# fire-fly.net
KiCad netlist of a schematic drawn in EAGLE
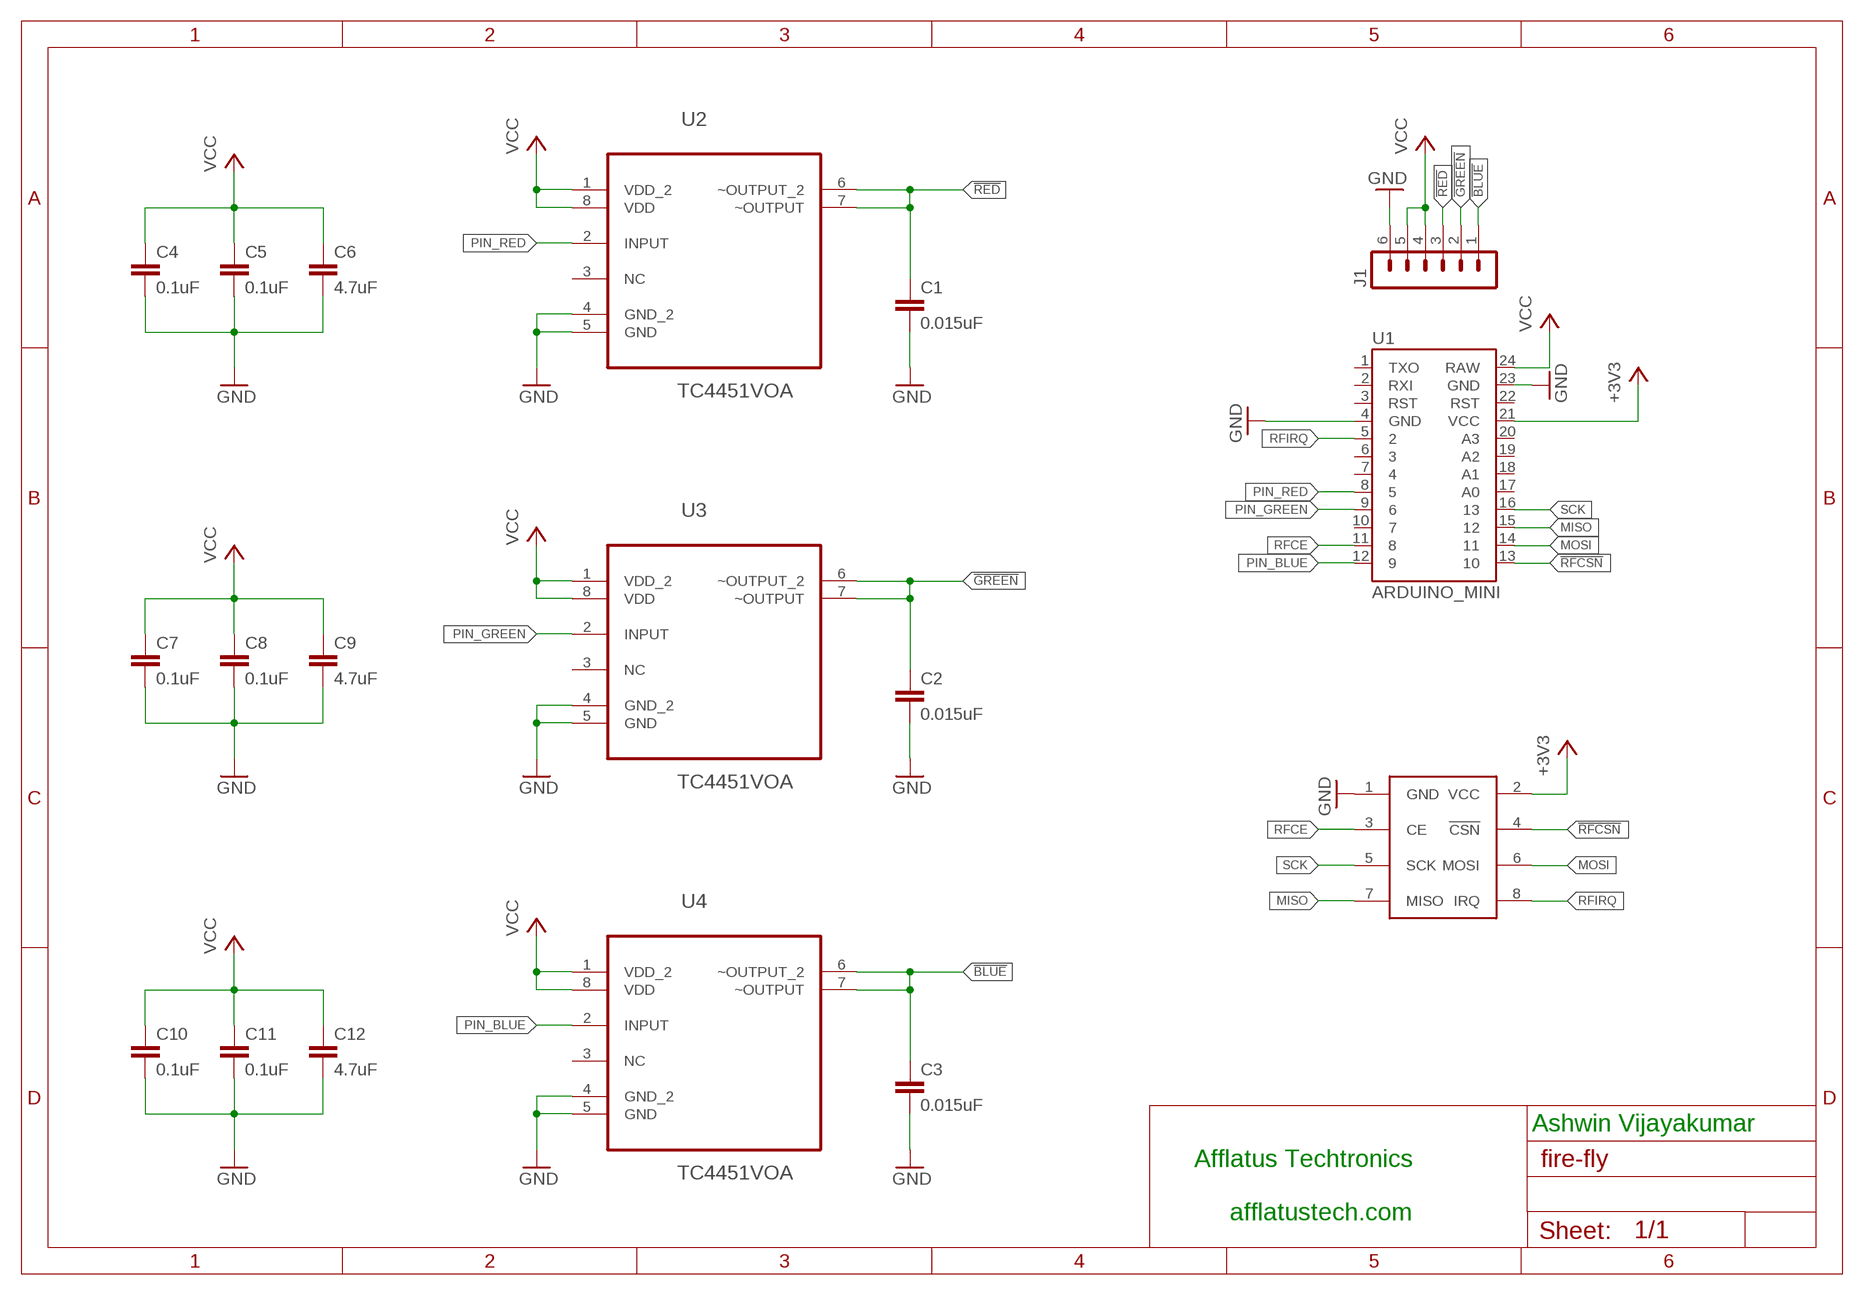
[diagram p0: schematic, sheet 1]

(export (version "E")
  (design (tool "Eeschema 10.0.6"))
  (components
    (comp (ref "C1")
      (value "0.015uF")
      (footprint "eagle-import:C1206")
      (libsource (lib "eagle-import") (part "C-EUC1206"))
    )
    (comp (ref "C2")
      (value "0.015uF")
      (footprint "eagle-import:C1206")
      (libsource (lib "eagle-import") (part "C-EUC1206"))
    )
    (comp (ref "C3")
      (value "0.015uF")
      (footprint "eagle-import:C1206")
      (libsource (lib "eagle-import") (part "C-EUC1206"))
    )
    (comp (ref "C4")
      (value "0.1uF")
      (footprint "eagle-import:C1206")
      (libsource (lib "eagle-import") (part "C-EUC1206"))
    )
    (comp (ref "C5")
      (value "0.1uF")
      (footprint "eagle-import:C1206")
      (libsource (lib "eagle-import") (part "C-EUC1206"))
    )
    (comp (ref "C6")
      (value "4.7uF")
      (footprint "eagle-import:C1206")
      (libsource (lib "eagle-import") (part "C-EUC1206"))
    )
    (comp (ref "C7")
      (value "0.1uF")
      (footprint "eagle-import:C1206")
      (libsource (lib "eagle-import") (part "C-EUC1206"))
    )
    (comp (ref "C8")
      (value "0.1uF")
      (footprint "eagle-import:C1206")
      (libsource (lib "eagle-import") (part "C-EUC1206"))
    )
    (comp (ref "C9")
      (value "4.7uF")
      (footprint "eagle-import:C1206")
      (libsource (lib "eagle-import") (part "C-EUC1206"))
    )
    (comp (ref "C10")
      (value "0.1uF")
      (footprint "eagle-import:C1206")
      (libsource (lib "eagle-import") (part "C-EUC1206"))
    )
    (comp (ref "C11")
      (value "0.1uF")
      (footprint "eagle-import:C1206")
      (libsource (lib "eagle-import") (part "C-EUC1206"))
    )
    (comp (ref "C12")
      (value "4.7uF")
      (footprint "eagle-import:C1206")
      (libsource (lib "eagle-import") (part "C-EUC1206"))
    )
    (comp (ref "J1")
      (value "MA06-1")
      (footprint "eagle-import:MA06-1")
      (libsource (lib "eagle-import") (part "MA06-1"))
    )
    (comp (ref "U$1")
      (value "NRF24L01_MODULE")
      (footprint "eagle-import:NRF24L01_MODULE")
      (libsource (lib "eagle-import") (part "NRF24L01_MODULE"))
    )
    (comp (ref "U1")
      (value "ARDUINO_MINI")
      (footprint "eagle-import:ARDUINO_MINI")
      (libsource (lib "eagle-import") (part "ARDUINO_MINI"))
    )
    (comp (ref "U2")
      (value "TC4451VOA")
      (footprint "eagle-import:SOIC127P600X175-8N")
      (libsource (lib "eagle-import") (part "TC4451VOA"))
    )
    (comp (ref "U3")
      (value "TC4451VOA")
      (footprint "eagle-import:SOIC127P600X175-8N")
      (libsource (lib "eagle-import") (part "TC4451VOA"))
    )
    (comp (ref "U4")
      (value "TC4451VOA")
      (footprint "eagle-import:SOIC127P600X175-8N")
      (libsource (lib "eagle-import") (part "TC4451VOA"))
    )
  )
  (nets
    (net (code "1") (name "+3V3") (class "Default")
      (node (ref "U$1") (pin "2") (pinfunction "VCC_2") (pintype "power_in"))
      (node (ref "U1") (pin "21") (pinfunction "VCC_21") (pintype "bidirectional"))
    )
    (net (code "2") (name "/~{BLUE}") (class "Default")
      (node (ref "C3") (pin "1") (pinfunction "1_1") (pintype "passive"))
      (node (ref "J1") (pin "1") (pinfunction "1_1") (pintype "passive"))
      (node (ref "U4") (pin "6") (pinfunction "~{OUTPUT_2}_6") (pintype "output"))
      (node (ref "U4") (pin "7") (pinfunction "~{OUTPUT}_7") (pintype "output"))
    )
    (net (code "3") (name "/~{GREEN}") (class "Default")
      (node (ref "C2") (pin "1") (pinfunction "1_1") (pintype "passive"))
      (node (ref "J1") (pin "2") (pinfunction "2_2") (pintype "passive"))
      (node (ref "U3") (pin "6") (pinfunction "~{OUTPUT_2}_6") (pintype "output"))
      (node (ref "U3") (pin "7") (pinfunction "~{OUTPUT}_7") (pintype "output"))
    )
    (net (code "4") (name "/~{RED}") (class "Default")
      (node (ref "C1") (pin "1") (pinfunction "1_1") (pintype "passive"))
      (node (ref "J1") (pin "3") (pinfunction "3_3") (pintype "passive"))
      (node (ref "U2") (pin "6") (pinfunction "~{OUTPUT_2}_6") (pintype "output"))
      (node (ref "U2") (pin "7") (pinfunction "~{OUTPUT}_7") (pintype "output"))
    )
    (net (code "5") (name "/~{RFCSN}") (class "Default")
      (node (ref "U$1") (pin "4") (pinfunction "~{CSN}_4") (pintype "input"))
      (node (ref "U1") (pin "13") (pinfunction "10_13") (pintype "bidirectional"))
    )
    (net (code "6") (name "GND") (class "Default")
      (node (ref "C1") (pin "2") (pinfunction "2_2") (pintype "passive"))
      (node (ref "C10") (pin "2") (pinfunction "2_2") (pintype "passive"))
      (node (ref "C11") (pin "2") (pinfunction "2_2") (pintype "passive"))
      (node (ref "C12") (pin "2") (pinfunction "2_2") (pintype "passive"))
      (node (ref "C2") (pin "2") (pinfunction "2_2") (pintype "passive"))
      (node (ref "C3") (pin "2") (pinfunction "2_2") (pintype "passive"))
      (node (ref "C4") (pin "2") (pinfunction "2_2") (pintype "passive"))
      (node (ref "C5") (pin "2") (pinfunction "2_2") (pintype "passive"))
      (node (ref "C6") (pin "2") (pinfunction "2_2") (pintype "passive"))
      (node (ref "C7") (pin "2") (pinfunction "2_2") (pintype "passive"))
      (node (ref "C8") (pin "2") (pinfunction "2_2") (pintype "passive"))
      (node (ref "C9") (pin "2") (pinfunction "2_2") (pintype "passive"))
      (node (ref "J1") (pin "6") (pinfunction "6_6") (pintype "passive"))
      (node (ref "U$1") (pin "1") (pinfunction "GND_1") (pintype "power_in"))
      (node (ref "U1") (pin "23") (pinfunction "GND_23") (pintype "bidirectional"))
      (node (ref "U1") (pin "4") (pinfunction "GND_4") (pintype "bidirectional"))
      (node (ref "U2") (pin "4") (pinfunction "GND_2_4") (pintype "passive"))
      (node (ref "U2") (pin "5") (pinfunction "GND_5") (pintype "passive"))
      (node (ref "U3") (pin "4") (pinfunction "GND_2_4") (pintype "passive"))
      (node (ref "U3") (pin "5") (pinfunction "GND_5") (pintype "passive"))
      (node (ref "U4") (pin "4") (pinfunction "GND_2_4") (pintype "passive"))
      (node (ref "U4") (pin "5") (pinfunction "GND_5") (pintype "passive"))
    )
    (net (code "7") (name "MISO") (class "Default")
      (node (ref "U$1") (pin "7") (pinfunction "MISO_7") (pintype "output"))
      (node (ref "U1") (pin "15") (pinfunction "12_15") (pintype "bidirectional"))
    )
    (net (code "8") (name "MOSI") (class "Default")
      (node (ref "U$1") (pin "6") (pinfunction "MOSI_6") (pintype "input"))
      (node (ref "U1") (pin "14") (pinfunction "11_14") (pintype "bidirectional"))
    )
    (net (code "9") (name "PIN_BLUE") (class "Default")
      (node (ref "U1") (pin "12") (pinfunction "9_12") (pintype "bidirectional"))
      (node (ref "U4") (pin "2") (pinfunction "INPUT_2") (pintype "input"))
    )
    (net (code "10") (name "PIN_GREEN") (class "Default")
      (node (ref "U1") (pin "9") (pinfunction "6_9") (pintype "bidirectional"))
      (node (ref "U3") (pin "2") (pinfunction "INPUT_2") (pintype "input"))
    )
    (net (code "11") (name "PIN_RED") (class "Default")
      (node (ref "U1") (pin "8") (pinfunction "5_8") (pintype "bidirectional"))
      (node (ref "U2") (pin "2") (pinfunction "INPUT_2") (pintype "input"))
    )
    (net (code "12") (name "RFCE") (class "Default")
      (node (ref "U$1") (pin "3") (pinfunction "CE_3") (pintype "input"))
      (node (ref "U1") (pin "11") (pinfunction "8_11") (pintype "bidirectional"))
    )
    (net (code "13") (name "RFIRQ") (class "Default")
      (node (ref "U$1") (pin "8") (pinfunction "IRQ_8") (pintype "output"))
      (node (ref "U1") (pin "5") (pinfunction "2_5") (pintype "bidirectional"))
    )
    (net (code "14") (name "SCK") (class "Default")
      (node (ref "U$1") (pin "5") (pinfunction "SCK_5") (pintype "input"))
      (node (ref "U1") (pin "16") (pinfunction "13_16") (pintype "bidirectional"))
    )
    (net (code "15") (name "VCC") (class "Default")
      (node (ref "C10") (pin "1") (pinfunction "1_1") (pintype "passive"))
      (node (ref "C11") (pin "1") (pinfunction "1_1") (pintype "passive"))
      (node (ref "C12") (pin "1") (pinfunction "1_1") (pintype "passive"))
      (node (ref "C4") (pin "1") (pinfunction "1_1") (pintype "passive"))
      (node (ref "C5") (pin "1") (pinfunction "1_1") (pintype "passive"))
      (node (ref "C6") (pin "1") (pinfunction "1_1") (pintype "passive"))
      (node (ref "C7") (pin "1") (pinfunction "1_1") (pintype "passive"))
      (node (ref "C8") (pin "1") (pinfunction "1_1") (pintype "passive"))
      (node (ref "C9") (pin "1") (pinfunction "1_1") (pintype "passive"))
      (node (ref "J1") (pin "4") (pinfunction "4_4") (pintype "passive"))
      (node (ref "J1") (pin "5") (pinfunction "5_5") (pintype "passive"))
      (node (ref "U1") (pin "24") (pinfunction "RAW_24") (pintype "bidirectional"))
      (node (ref "U2") (pin "1") (pinfunction "VDD_2_1") (pintype "power_in"))
      (node (ref "U2") (pin "8") (pinfunction "VDD_8") (pintype "power_in"))
      (node (ref "U3") (pin "1") (pinfunction "VDD_2_1") (pintype "power_in"))
      (node (ref "U3") (pin "8") (pinfunction "VDD_8") (pintype "power_in"))
      (node (ref "U4") (pin "1") (pinfunction "VDD_2_1") (pintype "power_in"))
      (node (ref "U4") (pin "8") (pinfunction "VDD_8") (pintype "power_in"))
    )
    (net (code "16") (name "unconnected-(U1-3-Pad6)") (class "Default")
      (node (ref "U1") (pin "6") (pinfunction "3_6") (pintype "bidirectional"))
    )
    (net (code "17") (name "unconnected-(U1-4-Pad7)") (class "Default")
      (node (ref "U1") (pin "7") (pinfunction "4_7") (pintype "bidirectional"))
    )
    (net (code "18") (name "unconnected-(U1-7-Pad10)") (class "Default")
      (node (ref "U1") (pin "10") (pinfunction "7_10") (pintype "bidirectional"))
    )
    (net (code "19") (name "unconnected-(U1-A0-Pad17)") (class "Default")
      (node (ref "U1") (pin "17") (pinfunction "A0_17") (pintype "bidirectional"))
    )
    (net (code "20") (name "unconnected-(U1-A1-Pad18)") (class "Default")
      (node (ref "U1") (pin "18") (pinfunction "A1_18") (pintype "bidirectional"))
    )
    (net (code "21") (name "unconnected-(U1-A2-Pad19)") (class "Default")
      (node (ref "U1") (pin "19") (pinfunction "A2_19") (pintype "bidirectional"))
    )
    (net (code "22") (name "unconnected-(U1-A3-Pad20)") (class "Default")
      (node (ref "U1") (pin "20") (pinfunction "A3_20") (pintype "bidirectional"))
    )
    (net (code "23") (name "unconnected-(U1-RST-Pad3)") (class "Default")
      (node (ref "U1") (pin "3") (pinfunction "RST_3") (pintype "bidirectional"))
    )
    (net (code "24") (name "unconnected-(U1-RST-Pad22)") (class "Default")
      (node (ref "U1") (pin "22") (pinfunction "RST_22") (pintype "bidirectional"))
    )
    (net (code "25") (name "unconnected-(U1-RXI-Pad2)") (class "Default")
      (node (ref "U1") (pin "2") (pinfunction "RXI_2") (pintype "bidirectional"))
    )
    (net (code "26") (name "unconnected-(U1-TXO-Pad1)") (class "Default")
      (node (ref "U1") (pin "1") (pinfunction "TXO_1") (pintype "bidirectional"))
    )
    (net (code "27") (name "unconnected-(U2-NC-Pad3)") (class "Default")
      (node (ref "U2") (pin "3") (pinfunction "NC_3") (pintype "no_connect"))
    )
    (net (code "28") (name "unconnected-(U3-NC-Pad3)") (class "Default")
      (node (ref "U3") (pin "3") (pinfunction "NC_3") (pintype "no_connect"))
    )
    (net (code "29") (name "unconnected-(U4-NC-Pad3)") (class "Default")
      (node (ref "U4") (pin "3") (pinfunction "NC_3") (pintype "no_connect"))
    )
  )
)
